# 3_FET_C.net
KiCad netlist of a schematic drawn in Altium Designer
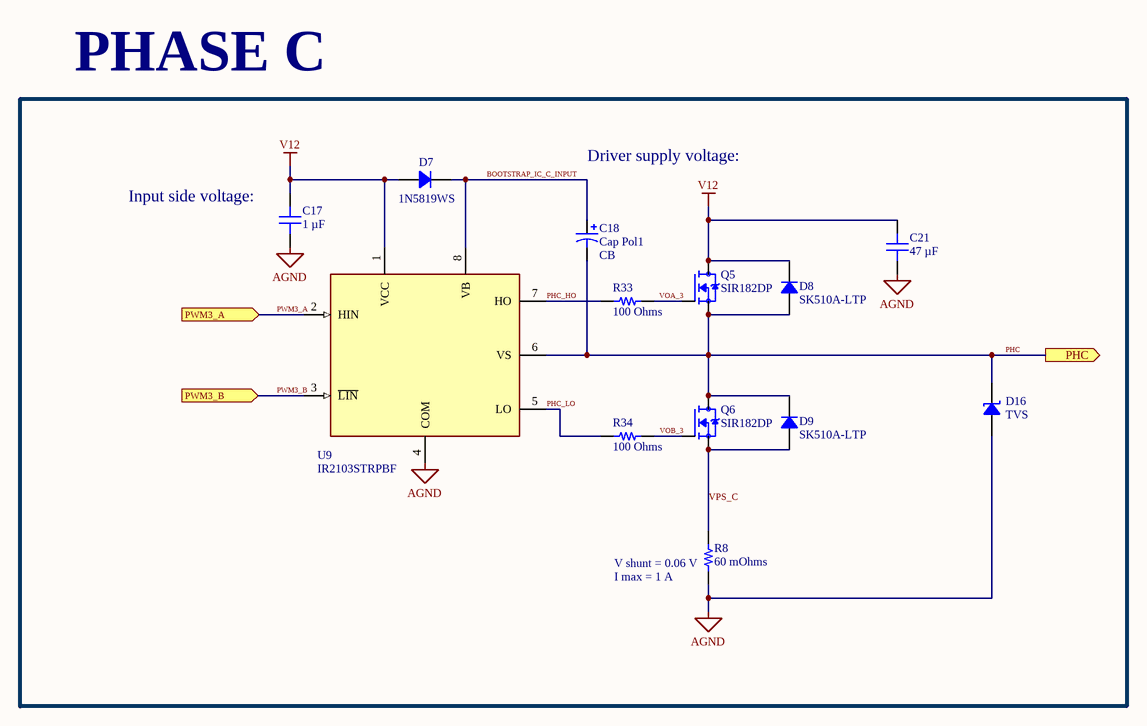
[diagram p0: 3_FET_C.SchDoc]

(export (version "E")
  (design (tool "Eeschema 10.0.6"))
  (components
    (comp (ref "C17")
      (value "1 µF")
      (footprint "CAP 0805_2012")
      (description "CAP CER 0.1UF 50V X7R 0805")
      (fields (field (name "PART NUMBER") "CC0805MRX7R9BB104") (field (name "MANUFACTURER") "Yageo"))
      (libsource (lib "Celestial Altium Library - altium_library") (part "Capacitor"))
    )
    (comp (ref "C18")
      (value "Cap Pol1")
      (footprint "CapacitorRadialElectrolytic")
      (description "Polarized Capacitor (Radial)")
      (fields (field (name "ALTIUM_VALUE") "CB") (field (name "PUBLISHER") "Altium Limited"))
      (libsource (lib "Miscellaneous Devices") (part "Cap Pol1"))
    )
    (comp (ref "C21")
      (value "47 µF")
      (footprint "CAP 1812_4532 1.1MM")
      (description "CAP1812 X5R 47UF 20% 6.3V")
      (fields
        (field (name "PART NUMBER") "GMC43X5R476M6R3NT")
        (field (name "MANUFACTURER") "Cal-Chip Electronics, Inc.")
      )
      (libsource (lib "Celestial Altium Library - altium_library") (part "Capacitor"))
    )
    (comp (ref "D7")
      (value "1N5819WS")
      (footprint "SOD-123")
      (description "DIODE SCHOTTKY 40V 1A SOD123")
      (fields (field (name "PART NUMBER") "1N5819HW-7-F") (field (name "MANUFACTURER") "Diodes Incorporated"))
      (libsource (lib "Celestial Altium Library - altium_library") (part "Diode"))
    )
    (comp (ref "D8")
      (value "SK510A-LTP")
      (footprint "DO214AC SMA")
      (description "DIODE SCHOTTKY 100V 5A DO214AC")
      (fields (field (name "MANUFACTURER") "Micro Commercial Co"))
      (libsource (lib "Celestial Altium Library - altium_library") (part "Diode"))
    )
    (comp (ref "D9")
      (value "SK510A-LTP")
      (footprint "DO214AC SMA")
      (description "DIODE SCHOTTKY 100V 5A DO214AC")
      (fields (field (name "MANUFACTURER") "Micro Commercial Co"))
      (libsource (lib "Celestial Altium Library - altium_library") (part "Diode"))
    )
    (comp (ref "D16")
      (value "TVS")
      (footprint "SMF DO-219AB")
      (description "TVS DIODE 57.6V 98V DO219AB")
      (fields
        (field (name "PART NUMBER") "VTVS58ASMF-HM3-08")
        (field (name "MANUFACTURER") "Vishay Semiconductor Diodes Division")
      )
      (libsource (lib "Celestial Altium Library - altium_library") (part "DIODE TVS UNI"))
    )
    (comp (ref "Q5")
      (value "SIR182DP")
      (footprint "TRANS_SIR182DP-T1-RE3")
      (description "N-Channel 60V 60A _Tc_ 69.4W _Tc_ Surface Mount PowerPAKÂ® SO-8")
      (fields (field (name "MP") "SIR182DP-T1-RE3") (field (name "MF") "Vishay Siliconix"))
      (libsource (lib "BLDC_BridgeBoard_V1") (part "SIR182DP-T1-RE3"))
    )
    (comp (ref "Q6")
      (value "SIR182DP")
      (footprint "TRANS_SIR182DP-T1-RE3")
      (description "N-Channel 60V 60A _Tc_ 69.4W _Tc_ Surface Mount PowerPAKÂ® SO-8")
      (fields (field (name "MP") "SIR182DP-T1-RE3") (field (name "MF") "Vishay Siliconix"))
      (libsource (lib "BLDC_BridgeBoard_V1") (part "SIR182DP-T1-RE3"))
    )
    (comp (ref "R8")
      (value "60 mOhms")
      (footprint "STACKPOLE CSR2512")
      (description "RES SMD 500 UOHM 1% 3W 2512")
      (fields (field (name "PART NUMBER") "CSR2512C0R0005F") (field (name "MANUFACTURER") "Riedon"))
      (libsource (lib "Celestial Altium Library - altium_library") (part "Resistor"))
    )
    (comp (ref "R33")
      (value "100 Ohms")
      (footprint "RES 0805_2012")
      (description "RES SMD 4.7K OHM 5% 1/2W 0805")
      (fields (field (name "PART NUMBER") "RCS08054K70JNEA") (field (name "MANUFACTURER") "Vishay Dale"))
      (libsource (lib "Celestial Altium Library - altium_library") (part "Resistor"))
    )
    (comp (ref "R34")
      (value "100 Ohms")
      (footprint "RES 0805_2012")
      (description "RES SMD 4.7K OHM 5% 1/2W 0805")
      (fields (field (name "PART NUMBER") "RCS08054K70JNEA") (field (name "MANUFACTURER") "Vishay Dale"))
      (libsource (lib "Celestial Altium Library - altium_library") (part "Resistor"))
    )
    (comp (ref "U9")
      (value "IR2103STRPBF")
      (footprint "Milibreria:SOIC8_IR2103STRPBF")
      (fields (field (name "MF") "Infineon"))
      (libsource (lib "BLDC_BridgeBoard_V1") (part "IR2103STRPBF"))
    )
  )
  (nets
    (net (code "1") (name "/BOOTSTRAP_IC_C_INPUT") (class "Default")
      (node (ref "C18") (pin "1") (pinfunction "1_1") (pintype "passive"))
      (node (ref "D7") (pin "2") (pinfunction "2_2") (pintype "passive"))
      (node (ref "U9") (pin "8") (pinfunction "VB_8") (pintype "power_in"))
    )
    (net (code "2") (name "/PHC") (class "Default")
      (node (ref "C18") (pin "2") (pinfunction "2_2") (pintype "passive"))
      (node (ref "D16") (pin "2") (pinfunction "2_2") (pintype "passive"))
      (node (ref "D8") (pin "1") (pinfunction "1_1") (pintype "passive"))
      (node (ref "D9") (pin "2") (pinfunction "2_2") (pintype "passive"))
      (node (ref "Q5") (pin "1") (pinfunction "S_1") (pintype "passive"))
      (node (ref "Q5") (pin "2") (pinfunction "S_2") (pintype "passive"))
      (node (ref "Q5") (pin "3") (pinfunction "S_3") (pintype "passive"))
      (node (ref "Q6") (pin "5") (pinfunction "D_5") (pintype "passive"))
      (node (ref "Q6") (pin "6") (pinfunction "D_6") (pintype "passive"))
      (node (ref "Q6") (pin "7") (pinfunction "D_7") (pintype "passive"))
      (node (ref "Q6") (pin "8") (pinfunction "D_8") (pintype "passive"))
      (node (ref "Q6") (pin "9") (pinfunction "D_9") (pintype "passive"))
      (node (ref "U9") (pin "6") (pinfunction "VS_6") (pintype "passive"))
    )
    (net (code "3") (name "/PHC_HO") (class "Default")
      (node (ref "R33") (pin "2") (pinfunction "2_2") (pintype "passive"))
      (node (ref "U9") (pin "7") (pinfunction "HO_7") (pintype "passive"))
    )
    (net (code "4") (name "/PHC_LO") (class "Default")
      (node (ref "R34") (pin "2") (pinfunction "2_2") (pintype "passive"))
      (node (ref "U9") (pin "5") (pinfunction "LO_5") (pintype "passive"))
    )
    (net (code "5") (name "/PWM3_A") (class "Default")
      (node (ref "U9") (pin "2") (pinfunction "HIN_2") (pintype "input"))
    )
    (net (code "6") (name "/PWM3_B") (class "Default")
      (node (ref "U9") (pin "3") (pinfunction "~{LIN}_3") (pintype "input"))
    )
    (net (code "7") (name "/VOA_3") (class "Default")
      (node (ref "Q5") (pin "4") (pinfunction "G_4") (pintype "passive"))
      (node (ref "R33") (pin "1") (pinfunction "1_1") (pintype "passive"))
    )
    (net (code "8") (name "/VOB_3") (class "Default")
      (node (ref "Q6") (pin "4") (pinfunction "G_4") (pintype "passive"))
      (node (ref "R34") (pin "1") (pinfunction "1_1") (pintype "passive"))
    )
    (net (code "9") (name "/VPS_C") (class "Default")
      (node (ref "D9") (pin "1") (pinfunction "1_1") (pintype "passive"))
      (node (ref "Q6") (pin "1") (pinfunction "S_1") (pintype "passive"))
      (node (ref "Q6") (pin "2") (pinfunction "S_2") (pintype "passive"))
      (node (ref "Q6") (pin "3") (pinfunction "S_3") (pintype "passive"))
      (node (ref "R8") (pin "2") (pinfunction "2_2") (pintype "passive"))
    )
    (net (code "10") (name "AGND") (class "Default")
      (node (ref "C17") (pin "1") (pinfunction "1_1") (pintype "passive"))
      (node (ref "C21") (pin "1") (pinfunction "1_1") (pintype "passive"))
      (node (ref "D16") (pin "1") (pinfunction "1_1") (pintype "passive"))
      (node (ref "R8") (pin "1") (pinfunction "1_1") (pintype "passive"))
      (node (ref "U9") (pin "4") (pinfunction "COM_4") (pintype "power_in"))
    )
    (net (code "11") (name "V12") (class "Default")
      (node (ref "C17") (pin "2") (pinfunction "2_2") (pintype "passive"))
      (node (ref "C21") (pin "2") (pinfunction "2_2") (pintype "passive"))
      (node (ref "D7") (pin "1") (pinfunction "1_1") (pintype "passive"))
      (node (ref "D8") (pin "2") (pinfunction "2_2") (pintype "passive"))
      (node (ref "Q5") (pin "5") (pinfunction "D_5") (pintype "passive"))
      (node (ref "Q5") (pin "6") (pinfunction "D_6") (pintype "passive"))
      (node (ref "Q5") (pin "7") (pinfunction "D_7") (pintype "passive"))
      (node (ref "Q5") (pin "8") (pinfunction "D_8") (pintype "passive"))
      (node (ref "Q5") (pin "9") (pinfunction "D_9") (pintype "passive"))
      (node (ref "U9") (pin "1") (pinfunction "VCC_1") (pintype "power_in"))
    )
  )
)
